# SoC_pwr_2.net
KiCad netlist of a schematic drawn in Altium Designer
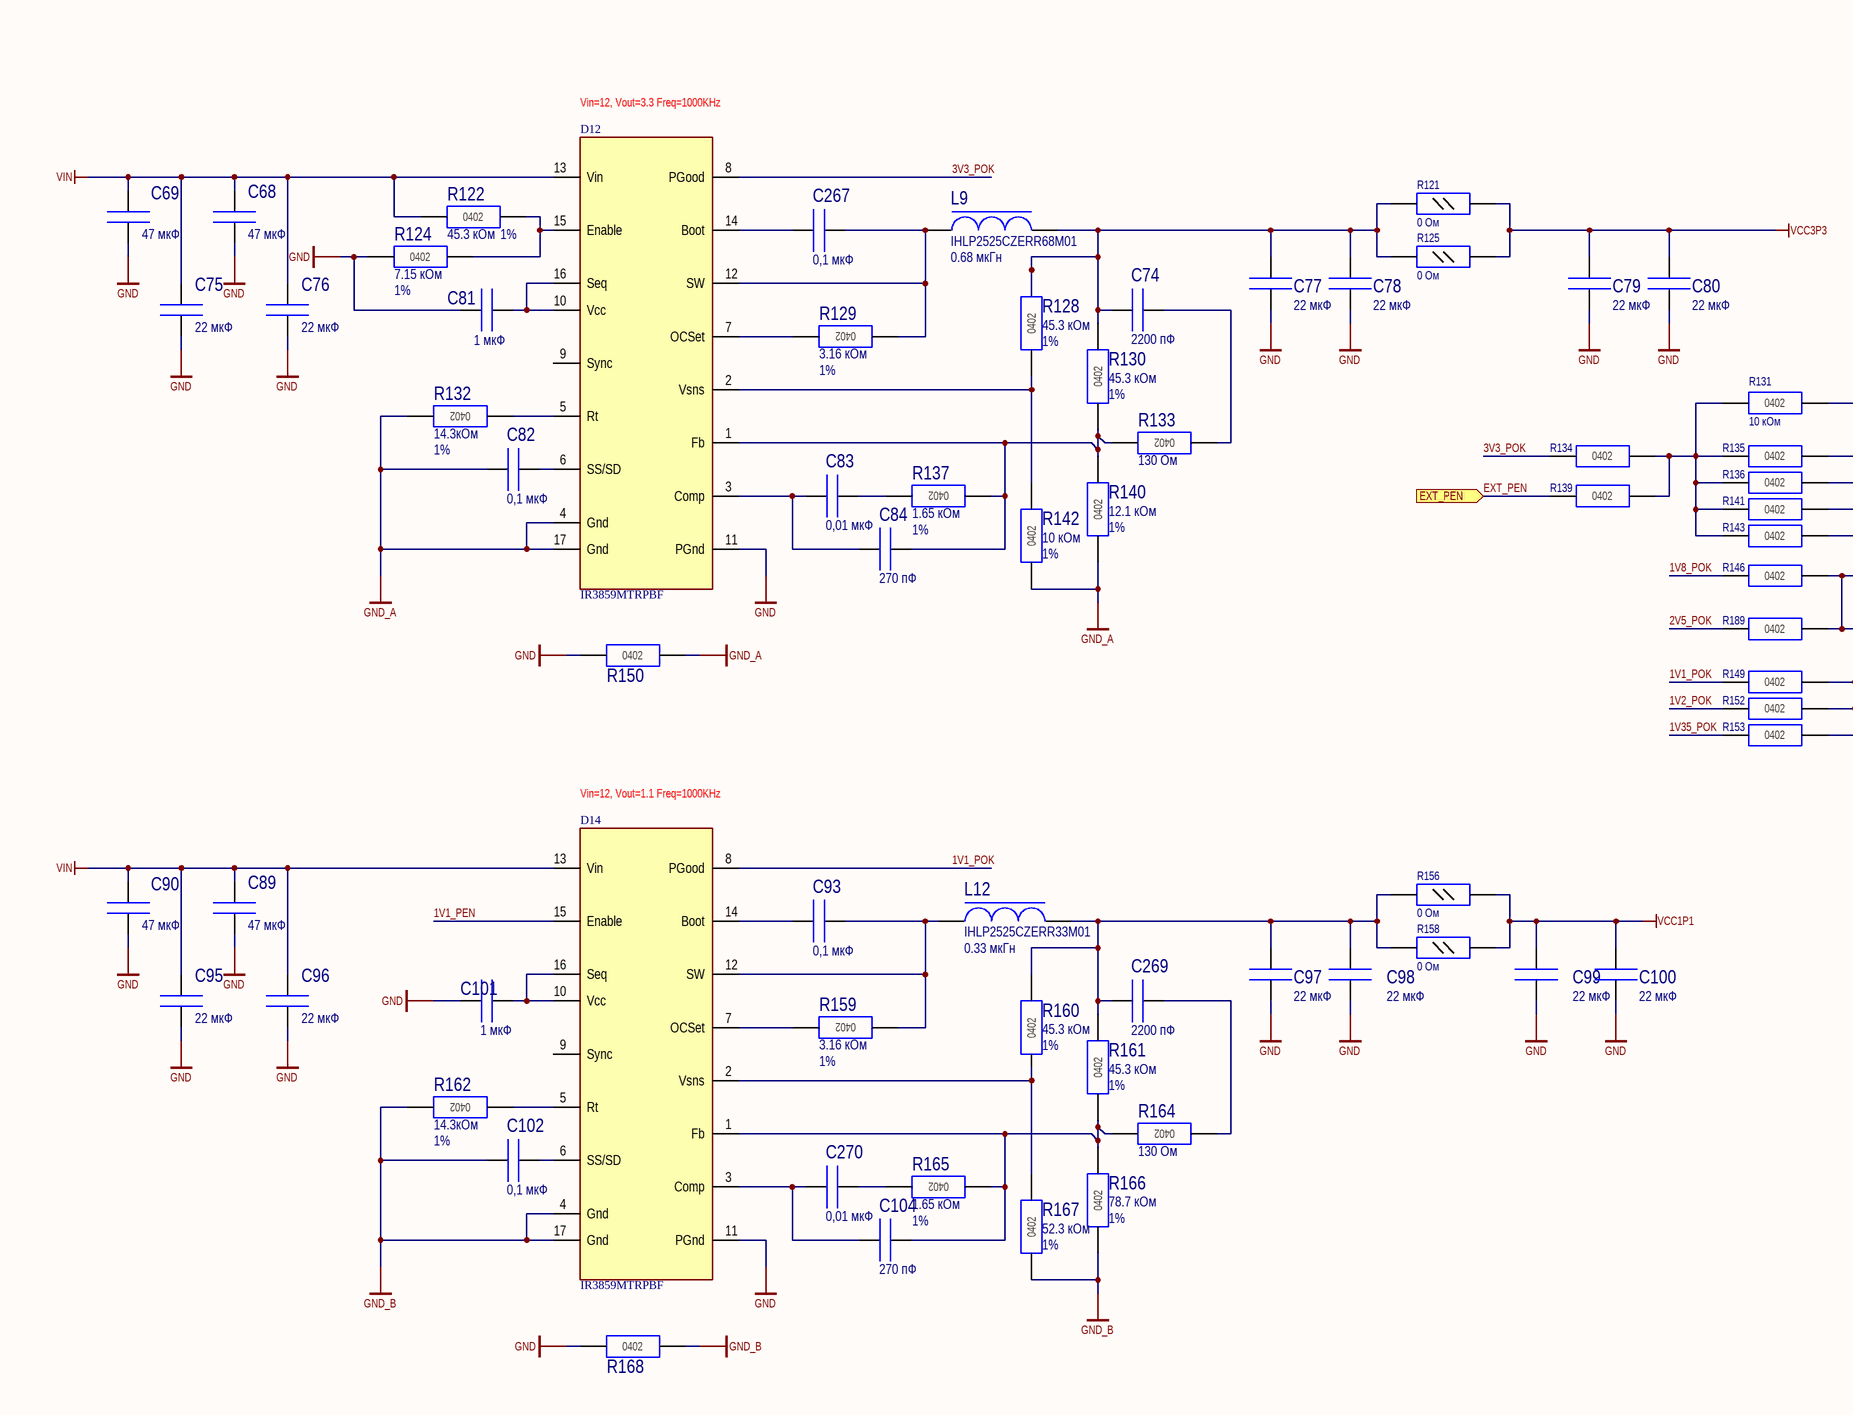
[diagram p0: SoC_pwr_2.SchDoc, left]
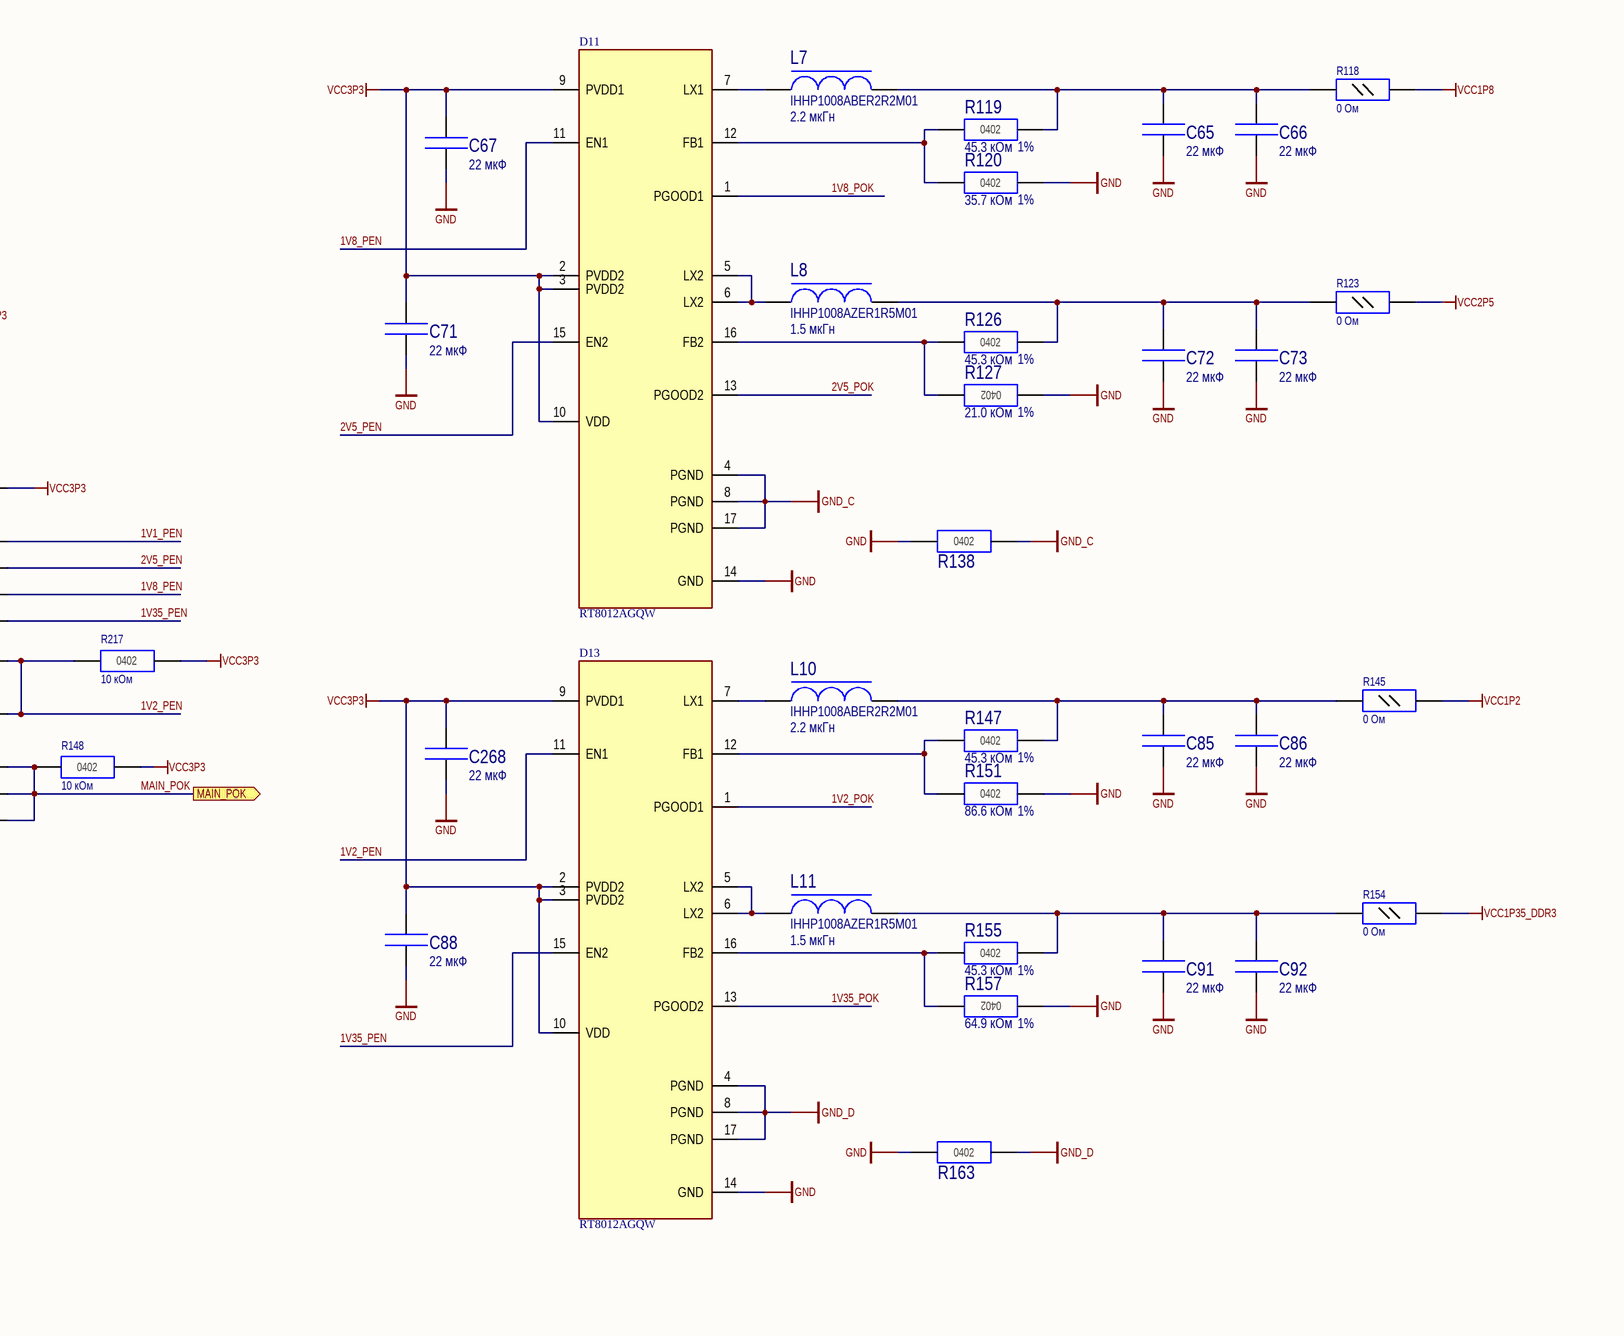
[diagram p1: SoC_pwr_2.SchDoc, right]

(export (version "E")
  (design (tool "Eeschema 10.0.6"))
  (components
    (comp (ref "C65")
      (value "22 мкФ")
      (footprint "CC0603")
      (description "Чип конденсатор керамический")
      (fields (field (name "Comment") "CC0603-X5R-22 мкФ-20%-6,3В"))
      (libsource (lib "Конденсаторы") (part "CC0603-X5R-#-20%-6,3В"))
    )
    (comp (ref "C66")
      (value "22 мкФ")
      (footprint "CC0603")
      (description "Чип конденсатор керамический")
      (fields (field (name "Comment") "CC0603-X5R-22 мкФ-20%-6,3В"))
      (libsource (lib "Конденсаторы") (part "CC0603-X5R-#-20%-6,3В"))
    )
    (comp (ref "C67")
      (value "22 мкФ")
      (footprint "CC0603")
      (description "Чип конденсатор керамический")
      (fields (field (name "Comment") "CC0603-X5R-22 мкФ-20%-6,3В"))
      (libsource (lib "Конденсаторы") (part "CC0603-X5R-#-20%-6,3В"))
    )
    (comp (ref "C68")
      (value "47 мкФ")
      (footprint "CC0603")
      (description "Чип конденсатор керамический")
      (fields (field (name "Comment") "CC0603-X5R-47 мкФ-20%-6,3В"))
      (libsource (lib "Конденсаторы") (part "CC0603-X5R-#-20%-6,3В"))
    )
    (comp (ref "C69")
      (value "47 мкФ")
      (footprint "CC0603")
      (description "Чип конденсатор керамический")
      (fields (field (name "Comment") "CC0603-X5R-47 мкФ-20%-6,3В"))
      (libsource (lib "Конденсаторы") (part "CC0603-X5R-#-20%-6,3В"))
    )
    (comp (ref "C71")
      (value "22 мкФ")
      (footprint "CC0603")
      (description "Чип конденсатор керамический")
      (fields (field (name "Comment") "CC0603-X5R-22 мкФ-20%-6,3В"))
      (libsource (lib "Конденсаторы") (part "CC0603-X5R-#-20%-6,3В"))
    )
    (comp (ref "C72")
      (value "22 мкФ")
      (footprint "CC0603")
      (description "Чип конденсатор керамический")
      (fields (field (name "Comment") "CC0603-X5R-22 мкФ-20%-6,3В"))
      (libsource (lib "Конденсаторы") (part "CC0603-X5R-#-20%-6,3В"))
    )
    (comp (ref "C73")
      (value "22 мкФ")
      (footprint "CC0603")
      (description "Чип конденсатор керамический")
      (fields (field (name "Comment") "CC0603-X5R-22 мкФ-20%-6,3В"))
      (libsource (lib "Конденсаторы") (part "CC0603-X5R-#-20%-6,3В"))
    )
    (comp (ref "C74")
      (value "2200 пФ")
      (footprint "CC0402(1005)")
      (description "Чип конденсатор керамический")
      (fields (field (name "Comment") "CC0402-X7R-2200 пФ-10%-16В"))
      (libsource (lib "Чип конденсаторы") (part "CC0402-X7R-#-20%-10В"))
    )
    (comp (ref "C75")
      (value "22 мкФ")
      (footprint "CC0603")
      (description "Чип конденсатор керамический")
      (fields (field (name "Comment") "CC0603-X5R-22 мкФ-20%-6,3В"))
      (libsource (lib "Конденсаторы") (part "CC0603-X5R-#-20%-6,3В"))
    )
    (comp (ref "C76")
      (value "22 мкФ")
      (footprint "CC0603")
      (description "Чип конденсатор керамический")
      (fields (field (name "Comment") "CC0603-X5R-22 мкФ-20%-6,3В"))
      (libsource (lib "Конденсаторы") (part "CC0603-X5R-#-20%-6,3В"))
    )
    (comp (ref "C77")
      (value "22 мкФ")
      (footprint "CC0603")
      (description "Чип конденсатор керамический")
      (fields (field (name "Comment") "CC0603-X5R-22 мкФ-20%-6,3В"))
      (libsource (lib "Конденсаторы") (part "CC0603-X5R-#-20%-6,3В"))
    )
    (comp (ref "C78")
      (value "22 мкФ")
      (footprint "CC0603")
      (description "Чип конденсатор керамический")
      (fields (field (name "Comment") "CC0603-X5R-22 мкФ-20%-6,3В"))
      (libsource (lib "Конденсаторы") (part "CC0603-X5R-#-20%-6,3В"))
    )
    (comp (ref "C79")
      (value "22 мкФ")
      (footprint "CC0603")
      (description "Чип конденсатор керамический")
      (fields (field (name "Comment") "CC0603-X5R-22 мкФ-20%-6,3В"))
      (libsource (lib "Конденсаторы") (part "CC0603-X5R-#-20%-6,3В"))
    )
    (comp (ref "C80")
      (value "22 мкФ")
      (footprint "CC0603")
      (description "Чип конденсатор керамический")
      (fields (field (name "Comment") "CC0603-X5R-22 мкФ-20%-6,3В"))
      (libsource (lib "Конденсаторы") (part "CC0603-X5R-#-20%-6,3В"))
    )
    (comp (ref "C81")
      (value "1 мкФ")
      (footprint "CC0603")
      (description "Чип конденсатор керамический")
      (fields (field (name "Comment") "CC0603-X5R-1 мкФ-10%-25В"))
      (libsource (lib "Конденсаторы") (part "CC0603-X5R-#-20%-6,3В"))
    )
    (comp (ref "C82")
      (value "0,1 мкФ")
      (footprint "CC0402(1005)")
      (description "Чип конденсатор керамический")
      (fields (field (name "Comment") "CC0402-X7R-0,1 мкФ-20%-10В"))
      (libsource (lib "Чип конденсаторы") (part "CC0402-X7R-#-20%-10В"))
    )
    (comp (ref "C83")
      (value "0,01 мкФ")
      (footprint "CC0402(1005)")
      (description "Чип конденсатор керамический")
      (fields (field (name "Comment") "CC0402-X7R-0,01 мкФ-10%-50В"))
      (libsource (lib "Чип конденсаторы") (part "CC0402-X7R-#-20%-10В"))
    )
    (comp (ref "C84")
      (value "270 пФ")
      (footprint "CC0402(1005)")
      (description "Чип конденсатор керамический")
      (fields (field (name "Comment") "CC0402-NP0-270 пФ-1%-50В"))
      (libsource (lib "Чип конденсаторы") (part "CC0402-X7R-#-20%-10В"))
    )
    (comp (ref "C85")
      (value "22 мкФ")
      (footprint "CC0603")
      (description "Чип конденсатор керамический")
      (fields (field (name "Comment") "CC0603-X5R-22 мкФ-20%-6,3В"))
      (libsource (lib "Конденсаторы") (part "CC0603-X5R-#-20%-6,3В"))
    )
    (comp (ref "C86")
      (value "22 мкФ")
      (footprint "CC0603")
      (description "Чип конденсатор керамический")
      (fields (field (name "Comment") "CC0603-X5R-22 мкФ-20%-6,3В"))
      (libsource (lib "Конденсаторы") (part "CC0603-X5R-#-20%-6,3В"))
    )
    (comp (ref "C88")
      (value "22 мкФ")
      (footprint "CC0603")
      (description "Чип конденсатор керамический")
      (fields (field (name "Comment") "CC0603-X5R-22 мкФ-20%-6,3В"))
      (libsource (lib "Конденсаторы") (part "CC0603-X5R-#-20%-6,3В"))
    )
    (comp (ref "C89")
      (value "47 мкФ")
      (footprint "CC0603")
      (description "Чип конденсатор керамический")
      (fields (field (name "Comment") "CC0603-X5R-47 мкФ-20%-6,3В"))
      (libsource (lib "Конденсаторы") (part "CC0603-X5R-#-20%-6,3В"))
    )
    (comp (ref "C90")
      (value "47 мкФ")
      (footprint "CC0603")
      (description "Чип конденсатор керамический")
      (fields (field (name "Comment") "CC0603-X5R-47 мкФ-20%-6,3В"))
      (libsource (lib "Конденсаторы") (part "CC0603-X5R-#-20%-6,3В"))
    )
    (comp (ref "C91")
      (value "22 мкФ")
      (footprint "CC0603")
      (description "Чип конденсатор керамический")
      (fields (field (name "Comment") "CC0603-X5R-22 мкФ-20%-6,3В"))
      (libsource (lib "Конденсаторы") (part "CC0603-X5R-#-20%-6,3В"))
    )
    (comp (ref "C92")
      (value "22 мкФ")
      (footprint "CC0603")
      (description "Чип конденсатор керамический")
      (fields (field (name "Comment") "CC0603-X5R-22 мкФ-20%-6,3В"))
      (libsource (lib "Конденсаторы") (part "CC0603-X5R-#-20%-6,3В"))
    )
    (comp (ref "C93")
      (value "0,1 мкФ")
      (footprint "CC0402(1005)")
      (description "Чип конденсатор керамический")
      (fields (field (name "Comment") "CC0402-X7R-0,1 мкФ-20%-10В"))
      (libsource (lib "Чип конденсаторы") (part "CC0402-X7R-#-20%-10В"))
    )
    (comp (ref "C95")
      (value "22 мкФ")
      (footprint "CC0603")
      (description "Чип конденсатор керамический")
      (fields (field (name "Comment") "CC0603-X5R-22 мкФ-20%-6,3В"))
      (libsource (lib "Конденсаторы") (part "CC0603-X5R-#-20%-6,3В"))
    )
    (comp (ref "C96")
      (value "22 мкФ")
      (footprint "CC0603")
      (description "Чип конденсатор керамический")
      (fields (field (name "Comment") "CC0603-X5R-22 мкФ-20%-6,3В"))
      (libsource (lib "Конденсаторы") (part "CC0603-X5R-#-20%-6,3В"))
    )
    (comp (ref "C97")
      (value "22 мкФ")
      (footprint "CC0603")
      (description "Чип конденсатор керамический")
      (fields (field (name "Comment") "CC0603-X5R-22 мкФ-20%-6,3В"))
      (libsource (lib "Конденсаторы") (part "CC0603-X5R-#-20%-6,3В"))
    )
    (comp (ref "C98")
      (value "22 мкФ")
      (footprint "CC0603")
      (description "Чип конденсатор керамический")
      (fields (field (name "Comment") "CC0603-X5R-22 мкФ-20%-6,3В"))
      (libsource (lib "Конденсаторы") (part "CC0603-X5R-#-20%-6,3В"))
    )
    (comp (ref "C99")
      (value "22 мкФ")
      (footprint "CC0603")
      (description "Чип конденсатор керамический")
      (fields (field (name "Comment") "CC0603-X5R-22 мкФ-20%-6,3В"))
      (libsource (lib "Конденсаторы") (part "CC0603-X5R-#-20%-6,3В"))
    )
    (comp (ref "C100")
      (value "22 мкФ")
      (footprint "CC0603")
      (description "Чип конденсатор керамический")
      (fields (field (name "Comment") "CC0603-X5R-22 мкФ-20%-6,3В"))
      (libsource (lib "Конденсаторы") (part "CC0603-X5R-#-20%-6,3В"))
    )
    (comp (ref "C101")
      (value "1 мкФ")
      (footprint "CC0603")
      (description "Чип конденсатор керамический")
      (fields (field (name "Comment") "CC0603-X5R-1 мкФ-10%-25В"))
      (libsource (lib "Конденсаторы") (part "CC0603-X5R-#-20%-6,3В"))
    )
    (comp (ref "C102")
      (value "0,1 мкФ")
      (footprint "CC0402(1005)")
      (description "Чип конденсатор керамический")
      (fields (field (name "Comment") "CC0402-X7R-0,1 мкФ-20%-10В"))
      (libsource (lib "Чип конденсаторы") (part "CC0402-X7R-#-20%-10В"))
    )
    (comp (ref "C104")
      (value "270 пФ")
      (footprint "CC0402(1005)")
      (description "Чип конденсатор керамический")
      (fields (field (name "Comment") "CC0402-NP0-270 пФ-1%-50В"))
      (libsource (lib "Чип конденсаторы") (part "CC0402-X7R-#-20%-10В"))
    )
    (comp (ref "C267")
      (value "0,1 мкФ")
      (footprint "CC0402(1005)")
      (description "Чип конденсатор керамический")
      (fields (field (name "Comment") "CC0402-X7R-0,1 мкФ-20%-10В"))
      (libsource (lib "Чип конденсаторы") (part "CC0402-X7R-#-20%-10В"))
    )
    (comp (ref "C268")
      (value "22 мкФ")
      (footprint "CC0603")
      (description "Чип конденсатор керамический")
      (fields (field (name "Comment") "CC0603-X5R-22 мкФ-20%-6,3В"))
      (libsource (lib "Конденсаторы") (part "CC0603-X5R-#-20%-6,3В"))
    )
    (comp (ref "C269")
      (value "2200 пФ")
      (footprint "CC0402(1005)")
      (description "Чип конденсатор керамический")
      (fields (field (name "Comment") "CC0402-X7R-2200 пФ-10%-16В"))
      (libsource (lib "Чип конденсаторы") (part "CC0402-X7R-#-20%-10В"))
    )
    (comp (ref "C270")
      (value "0,01 мкФ")
      (footprint "CC0402(1005)")
      (description "Чип конденсатор керамический")
      (fields (field (name "Comment") "CC0402-X7R-0,01 мкФ-10%-50В"))
      (libsource (lib "Чип конденсаторы") (part "CC0402-X7R-#-20%-10В"))
    )
    (comp (ref "D11")
      (value "RT8012AGQW")
      (footprint "RT8012AGQW")
      (libsource (lib "SD_IC") (part "RT8012AGQW"))
    )
    (comp (ref "D12")
      (value "IR3859MTRPBF")
      (footprint "IR3859")
      (description "IC REG BUCK ADJ 9A SYNC 17PQFN")
      (libsource (lib "SD_IC") (part "IR3859MPbF"))
    )
    (comp (ref "D13")
      (value "RT8012AGQW")
      (footprint "RT8012AGQW")
      (libsource (lib "SD_IC") (part "RT8012AGQW"))
    )
    (comp (ref "D14")
      (value "IR3859MTRPBF")
      (footprint "IR3859")
      (description "IC REG BUCK ADJ 9A SYNC 17PQFN")
      (libsource (lib "SD_IC") (part "IR3859MPbF"))
    )
    (comp (ref "L7")
      (value "IHHP1008ABER2R2M01")
      (footprint "INDC2720X12L")
      (description "FIXED IND 2.2UH 2.3A 90 MOHM SMD")
      (fields (field (name "ALTIUM_VALUE") "2.2 мкГн"))
      (libsource (lib "SD_IC") (part "L_VISH_IIHHP1008ABE"))
    )
    (comp (ref "L8")
      (value "IHHP1008AZER1R5M01")
      (footprint "INDC2720X12L")
      (description "FIXED IND 1.5UH 2.4A 96 MOHM SMD")
      (fields (field (name "ALTIUM_VALUE") "1.5 мкГн"))
      (libsource (lib "SD_IC") (part "L_VISH_IIHHP1008ABE_1"))
    )
    (comp (ref "L9")
      (value "IHLP2525CZERR68M01")
      (footprint "INDP6965X30L")
      (description "FIXED IND 680NH 15.5A 5.5 MOHM")
      (fields (field (name "ALTIUM_VALUE") "0.68 мкГн"))
      (libsource (lib "SD_IC") (part "L_VISH_IHLP2525CZERR68M01"))
    )
    (comp (ref "L10")
      (value "IHHP1008ABER2R2M01")
      (footprint "INDC2720X12L")
      (description "FIXED IND 2.2UH 2.3A 90 MOHM SMD")
      (fields (field (name "ALTIUM_VALUE") "2.2 мкГн"))
      (libsource (lib "SD_IC") (part "L_VISH_IIHHP1008ABE"))
    )
    (comp (ref "L11")
      (value "IHHP1008AZER1R5M01")
      (footprint "INDC2720X12L")
      (description "FIXED IND 1.5UH 2.4A 96 MOHM SMD")
      (fields (field (name "ALTIUM_VALUE") "1.5 мкГн"))
      (libsource (lib "SD_IC") (part "L_VISH_IIHHP1008ABE_1"))
    )
    (comp (ref "L12")
      (value "IHLP2525CZERR33M01")
      (footprint "INDP6965X30L")
      (description "FIXED IND 680NH 15.5A 5.5 MOHM")
      (fields (field (name "ALTIUM_VALUE") "0.33 мкГн"))
      (libsource (lib "SD_IC") (part "L_VISH_IHLP2525CZERR68M01"))
    )
    (comp (ref "R118")
      (value "0 Ом")
      (footprint "CR0805")
      (description "Чип резистор")
      (fields (field (name "Comment") "CR0805-0 Ом-±5%"))
      (libsource (lib "Резисторы") (part "CR0805-#-±5%"))
    )
    (comp (ref "R119")
      (value "45.3 кОм")
      (footprint "CR0402(1005)")
      (description "Чип резистор")
      (fields (field (name "TOLERANCE") "1%") (field (name "Comment") "CR0402-45.3 кОм-±1%"))
      (libsource (lib "Чип резисторы") (part "CR0402-#-±1%"))
    )
    (comp (ref "R120")
      (value "35.7 кОм")
      (footprint "CR0402(1005)")
      (description "Чип резистор")
      (fields (field (name "TOLERANCE") "1%") (field (name "Comment") "CR0402-35.7 кОм-±1%"))
      (libsource (lib "Чип резисторы") (part "CR0402-#-±1%"))
    )
    (comp (ref "R121")
      (value "0 Ом")
      (footprint "CR0805")
      (description "Чип резистор")
      (fields (field (name "Comment") "CR0805-0 Ом-±5%"))
      (libsource (lib "Резисторы") (part "CR0805-#-±5%"))
    )
    (comp (ref "R122")
      (value "45.3 кОм")
      (footprint "CR0402(1005)")
      (description "Чип резистор")
      (fields (field (name "TOLERANCE") "1%") (field (name "Comment") "CR0402-45.3 кОм-±1%"))
      (libsource (lib "Чип резисторы") (part "CR0402-#-±1%"))
    )
    (comp (ref "R123")
      (value "0 Ом")
      (footprint "CR0805")
      (description "Чип резистор")
      (fields (field (name "Comment") "CR0805-0 Ом-±5%"))
      (libsource (lib "Резисторы") (part "CR0805-#-±5%"))
    )
    (comp (ref "R124")
      (value "7.15 кОм")
      (footprint "CR0402(1005)")
      (description "Чип резистор")
      (fields (field (name "TOLERANCE") "1%") (field (name "Comment") "CR0402-7.15 кОм-±1%"))
      (libsource (lib "Чип резисторы") (part "CR0402-#-±1%"))
    )
    (comp (ref "R125")
      (value "0 Ом")
      (footprint "CR0805")
      (description "Чип резистор")
      (fields (field (name "Comment") "CR0805-0 Ом-±5%"))
      (libsource (lib "Резисторы") (part "CR0805-#-±5%"))
    )
    (comp (ref "R126")
      (value "45.3 кОм")
      (footprint "CR0402(1005)")
      (description "Чип резистор")
      (fields (field (name "TOLERANCE") "1%") (field (name "Comment") "CR0402-45.3 кОм-±1%"))
      (libsource (lib "Чип резисторы") (part "CR0402-#-±1%"))
    )
    (comp (ref "R127")
      (value "21.0 кОм")
      (footprint "CR0402(1005)")
      (description "Чип резистор")
      (fields (field (name "TOLERANCE") "1%") (field (name "Comment") "CR0402-21.0 кОм-±1%"))
      (libsource (lib "") (part "CR0402-#-±1%_1"))
    )
    (comp (ref "R128")
      (value "45.3 кОм")
      (footprint "CR0402(1005)")
      (description "Чип резистор")
      (fields (field (name "TOLERANCE") "1%") (field (name "Comment") "CR0402-45.3 кОм-±1%"))
      (libsource (lib "") (part "CR0402-#-±1%_2"))
    )
    (comp (ref "R129")
      (value "3.16 кОм")
      (footprint "CR0402(1005)")
      (description "Чип резистор")
      (fields (field (name "TOLERANCE") "1%") (field (name "Comment") "CR0402-3.16 кОм-±1%"))
      (libsource (lib "") (part "CR0402-#-±1%_1"))
    )
    (comp (ref "R130")
      (value "45.3 кОм")
      (footprint "CR0402(1005)")
      (description "Чип резистор")
      (fields (field (name "TOLERANCE") "1%") (field (name "Comment") "CR0402-45.3 кОм-±1%"))
      (libsource (lib "") (part "CR0402-#-±1%_2"))
    )
    (comp (ref "R131")
      (value "10 кОм")
      (footprint "CR0402(1005)")
      (description "Чип резистор")
      (fields (field (name "TOLERANCE") "5%") (field (name "Comment") "CR0402-10 кОм-±5%"))
      (libsource (lib "Резисторы") (part "CR0402-#-±5%"))
    )
    (comp (ref "R132")
      (value "14.3кОм")
      (footprint "CR0402(1005)")
      (description "Чип резистор")
      (fields (field (name "TOLERANCE") "1%") (field (name "Comment") "CR0402-14.3кОм-±1%"))
      (libsource (lib "") (part "CR0402-#-±1%_1"))
    )
    (comp (ref "R133")
      (value "130 Ом")
      (footprint "CR0402(1005)")
      (description "Чип резистор")
      (fields (field (name "Comment") "CR0402-130 Ом-±1%"))
      (libsource (lib "") (part "CR0402-#-±1%_1"))
    )
    (comp (ref "R134")
      (value "CR0402-0 Ом-±5%")
      (footprint "CR0402(1005)")
      (description "Чип резистор")
      (fields (field (name "TOLERANCE") "5%"))
      (libsource (lib "Резисторы") (part "CR0402-#-±5%"))
    )
    (comp (ref "R135")
      (value "CR0402-0 Ом-±5%")
      (footprint "CR0402(1005)")
      (description "Чип резистор")
      (fields (field (name "TOLERANCE") "5%"))
      (libsource (lib "Резисторы") (part "CR0402-#-±5%"))
    )
    (comp (ref "R136")
      (value "CR0402-0 Ом-±5%")
      (footprint "CR0402(1005)")
      (description "Чип резистор")
      (fields (field (name "TOLERANCE") "5%"))
      (libsource (lib "Резисторы") (part "CR0402-#-±5%"))
    )
    (comp (ref "R137")
      (value "1.65 кОм")
      (footprint "CR0402(1005)")
      (description "Чип резистор")
      (fields (field (name "TOLERANCE") "1%") (field (name "Comment") "CR0402-1.65 кОм-±1%"))
      (libsource (lib "") (part "CR0402-#-±1%_1"))
    )
    (comp (ref "R138")
      (value "CR0402-0 Ом-±5%")
      (footprint "CR0402(1005)")
      (description "Чип резистор")
      (fields (field (name "TOLERANCE") "5%"))
      (libsource (lib "Резисторы") (part "CR0402-#-±5%"))
    )
    (comp (ref "R139")
      (value "CR0402-0 Ом-±5%")
      (footprint "CR0402(1005)")
      (description "Чип резистор")
      (fields (field (name "TOLERANCE") "5%"))
      (libsource (lib "Резисторы") (part "CR0402-#-±5%"))
    )
    (comp (ref "R140")
      (value "12.1 кОм")
      (footprint "CR0402(1005)")
      (description "Чип резистор")
      (fields (field (name "TOLERANCE") "1%") (field (name "Comment") "CR0402-12.1 кОм-±1%"))
      (libsource (lib "") (part "CR0402-#-±1%_2"))
    )
    (comp (ref "R141")
      (value "CR0402-0 Ом-±5%")
      (footprint "CR0402(1005)")
      (description "Чип резистор")
      (fields (field (name "TOLERANCE") "5%"))
      (libsource (lib "Резисторы") (part "CR0402-#-±5%"))
    )
    (comp (ref "R142")
      (value "10 кОм")
      (footprint "CR0402(1005)")
      (description "Чип резистор")
      (fields (field (name "TOLERANCE") "1%") (field (name "Comment") "CR0402-10 кОм-±1%"))
      (libsource (lib "") (part "CR0402-#-±1%_2"))
    )
    (comp (ref "R143")
      (value "CR0402-0 Ом-±5%")
      (footprint "CR0402(1005)")
      (description "Чип резистор")
      (fields (field (name "TOLERANCE") "5%"))
      (libsource (lib "Резисторы") (part "CR0402-#-±5%"))
    )
    (comp (ref "R145")
      (value "0 Ом")
      (footprint "CR0805")
      (description "Чип резистор")
      (fields (field (name "Comment") "CR0805-0 Ом-±5%"))
      (libsource (lib "Резисторы") (part "CR0805-#-±5%"))
    )
    (comp (ref "R146")
      (value "CR0402-0 Ом-±5%")
      (footprint "CR0402(1005)")
      (description "Чип резистор")
      (fields (field (name "TOLERANCE") "5%"))
      (libsource (lib "Резисторы") (part "CR0402-#-±5%"))
    )
    (comp (ref "R147")
      (value "45.3 кОм")
      (footprint "CR0402(1005)")
      (description "Чип резистор")
      (fields (field (name "TOLERANCE") "1%") (field (name "Comment") "CR0402-45.3 кОм-±1%"))
      (libsource (lib "Чип резисторы") (part "CR0402-#-±1%"))
    )
    (comp (ref "R148")
      (value "10 кОм")
      (footprint "CR0402(1005)")
      (description "Чип резистор")
      (fields (field (name "TOLERANCE") "5%") (field (name "Comment") "CR0402-10 кОм-±5%"))
      (libsource (lib "Резисторы") (part "CR0402-#-±5%"))
    )
    (comp (ref "R149")
      (value "CR0402-0 Ом-±5%")
      (footprint "CR0402(1005)")
      (description "Чип резистор")
      (fields (field (name "TOLERANCE") "5%"))
      (libsource (lib "Резисторы") (part "CR0402-#-±5%"))
    )
    (comp (ref "R150")
      (value "CR0402-0 Ом-±5%")
      (footprint "CR0402(1005)")
      (description "Чип резистор")
      (fields (field (name "TOLERANCE") "5%"))
      (libsource (lib "Резисторы") (part "CR0402-#-±5%"))
    )
    (comp (ref "R151")
      (value "86.6 кОм")
      (footprint "CR0402(1005)")
      (description "Чип резистор")
      (fields (field (name "TOLERANCE") "1%") (field (name "Comment") "CR0402-86.6 кОм-±1%"))
      (libsource (lib "Чип резисторы") (part "CR0402-#-±1%"))
    )
    (comp (ref "R152")
      (value "CR0402-0 Ом-±5%")
      (footprint "CR0402(1005)")
      (description "Чип резистор")
      (fields (field (name "TOLERANCE") "5%"))
      (libsource (lib "Резисторы") (part "CR0402-#-±5%"))
    )
    (comp (ref "R153")
      (value "CR0402-0 Ом-±5%")
      (footprint "CR0402(1005)")
      (description "Чип резистор")
      (fields (field (name "TOLERANCE") "5%"))
      (libsource (lib "Резисторы") (part "CR0402-#-±5%"))
    )
    (comp (ref "R154")
      (value "0 Ом")
      (footprint "CR0805")
      (description "Чип резистор")
      (fields (field (name "Comment") "CR0805-0 Ом-±5%"))
      (libsource (lib "Резисторы") (part "CR0805-#-±5%"))
    )
    (comp (ref "R155")
      (value "45.3 кОм")
      (footprint "CR0402(1005)")
      (description "Чип резистор")
      (fields (field (name "TOLERANCE") "1%") (field (name "Comment") "CR0402-45.3 кОм-±1%"))
      (libsource (lib "Чип резисторы") (part "CR0402-#-±1%"))
    )
    (comp (ref "R156")
      (value "0 Ом")
      (footprint "CR0805")
      (description "Чип резистор")
      (fields (field (name "Comment") "CR0805-0 Ом-±5%"))
      (libsource (lib "Резисторы") (part "CR0805-#-±5%"))
    )
    (comp (ref "R157")
      (value "64.9 кОм")
      (footprint "CR0402(1005)")
      (description "Чип резистор")
      (fields (field (name "TOLERANCE") "1%") (field (name "Comment") "CR0402-64.9 кОм-±1%"))
      (libsource (lib "") (part "CR0402-#-±1%_1"))
    )
    (comp (ref "R158")
      (value "0 Ом")
      (footprint "CR0805")
      (description "Чип резистор")
      (fields (field (name "Comment") "CR0805-0 Ом-±5%"))
      (libsource (lib "Резисторы") (part "CR0805-#-±5%"))
    )
    (comp (ref "R159")
      (value "3.16 кОм")
      (footprint "CR0402(1005)")
      (description "Чип резистор")
      (fields (field (name "TOLERANCE") "1%") (field (name "Comment") "CR0402-3.16 кОм-±1%"))
      (libsource (lib "") (part "CR0402-#-±1%_1"))
    )
    (comp (ref "R160")
      (value "45.3 кОм")
      (footprint "CR0402(1005)")
      (description "Чип резистор")
      (fields (field (name "TOLERANCE") "1%") (field (name "Comment") "CR0402-45.3 кОм-±1%"))
      (libsource (lib "") (part "CR0402-#-±1%_2"))
    )
    (comp (ref "R161")
      (value "45.3 кОм")
      (footprint "CR0402(1005)")
      (description "Чип резистор")
      (fields (field (name "TOLERANCE") "1%") (field (name "Comment") "CR0402-45.3 кОм-±1%"))
      (libsource (lib "") (part "CR0402-#-±1%_2"))
    )
    (comp (ref "R162")
      (value "14.3кОм")
      (footprint "CR0402(1005)")
      (description "Чип резистор")
      (fields (field (name "TOLERANCE") "1%") (field (name "Comment") "CR0402-14.3кОм-±1%"))
      (libsource (lib "") (part "CR0402-#-±1%_1"))
    )
    (comp (ref "R163")
      (value "CR0402-0 Ом-±5%")
      (footprint "CR0402(1005)")
      (description "Чип резистор")
      (fields (field (name "TOLERANCE") "5%"))
      (libsource (lib "Резисторы") (part "CR0402-#-±5%"))
    )
    (comp (ref "R164")
      (value "130 Ом")
      (footprint "CR0402(1005)")
      (description "Чип резистор")
      (fields (field (name "Comment") "CR0402-130 Ом-±1%"))
      (libsource (lib "") (part "CR0402-#-±1%_1"))
    )
    (comp (ref "R165")
      (value "1.65 кОм")
      (footprint "CR0402(1005)")
      (description "Чип резистор")
      (fields (field (name "TOLERANCE") "1%") (field (name "Comment") "CR0402-1.65 кОм-±1%"))
      (libsource (lib "") (part "CR0402-#-±1%_1"))
    )
    (comp (ref "R166")
      (value "78.7 кОм")
      (footprint "CR0402(1005)")
      (description "Чип резистор")
      (fields (field (name "TOLERANCE") "1%") (field (name "Comment") "CR0402-78.7 кОм-±1%"))
      (libsource (lib "") (part "CR0402-#-±1%_2"))
    )
    (comp (ref "R167")
      (value "52.3 кОм")
      (footprint "CR0402(1005)")
      (description "Чип резистор")
      (fields (field (name "TOLERANCE") "1%") (field (name "Comment") "CR0402-52.3 кОм-±1%"))
      (libsource (lib "") (part "CR0402-#-±1%_2"))
    )
    (comp (ref "R168")
      (value "CR0402-0 Ом-±5%")
      (footprint "CR0402(1005)")
      (description "Чип резистор")
      (fields (field (name "TOLERANCE") "5%"))
      (libsource (lib "Резисторы") (part "CR0402-#-±5%"))
    )
    (comp (ref "R189")
      (value "CR0402-0 Ом-±5%")
      (footprint "CR0402(1005)")
      (description "Чип резистор")
      (fields (field (name "TOLERANCE") "5%"))
      (libsource (lib "Резисторы") (part "CR0402-#-±5%"))
    )
    (comp (ref "R217")
      (value "10 кОм")
      (footprint "CR0402(1005)")
      (description "Чип резистор")
      (fields (field (name "TOLERANCE") "5%") (field (name "Comment") "CR0402-10 кОм-±5%"))
      (libsource (lib "Резисторы") (part "CR0402-#-±5%"))
    )
  )
  (nets
    (net (code "1") (name "/1V1_PEN") (class "Default")
      (node (ref "D14") (pin "15") (pinfunction "Enable_15") (pintype "passive"))
      (node (ref "R135") (pin "2") (pinfunction "-_2") (pintype "passive"))
    )
    (net (code "2") (name "/1V1_POK") (class "Default")
      (node (ref "D14") (pin "8") (pinfunction "PGood_8") (pintype "passive"))
      (node (ref "R149") (pin "1") (pinfunction "+_1") (pintype "passive"))
    )
    (net (code "3") (name "/1V2_PEN") (class "Default")
      (node (ref "D13") (pin "11") (pinfunction "EN1_11") (pintype "passive"))
      (node (ref "R146") (pin "2") (pinfunction "-_2") (pintype "passive"))
      (node (ref "R189") (pin "2") (pinfunction "-_2") (pintype "passive"))
      (node (ref "R217") (pin "1") (pinfunction "+_1") (pintype "passive"))
    )
    (net (code "4") (name "/1V2_POK") (class "Default")
      (node (ref "D13") (pin "1") (pinfunction "PGOOD1_1") (pintype "passive"))
      (node (ref "R152") (pin "1") (pinfunction "+_1") (pintype "passive"))
    )
    (net (code "5") (name "/1V8_PEN") (class "Default")
      (node (ref "D11") (pin "11") (pinfunction "EN1_11") (pintype "passive"))
      (node (ref "R141") (pin "2") (pinfunction "-_2") (pintype "passive"))
    )
    (net (code "6") (name "/1V8_POK") (class "Default")
      (node (ref "D11") (pin "1") (pinfunction "PGOOD1_1") (pintype "passive"))
      (node (ref "R146") (pin "1") (pinfunction "+_1") (pintype "passive"))
    )
    (net (code "7") (name "/1V35_PEN") (class "Default")
      (node (ref "D13") (pin "15") (pinfunction "EN2_15") (pintype "passive"))
      (node (ref "R143") (pin "2") (pinfunction "-_2") (pintype "passive"))
    )
    (net (code "8") (name "/1V35_POK") (class "Default")
      (node (ref "D13") (pin "13") (pinfunction "PGOOD2_13") (pintype "passive"))
      (node (ref "R153") (pin "1") (pinfunction "+_1") (pintype "passive"))
    )
    (net (code "9") (name "/2V5_PEN") (class "Default")
      (node (ref "D11") (pin "15") (pinfunction "EN2_15") (pintype "passive"))
      (node (ref "R136") (pin "2") (pinfunction "-_2") (pintype "passive"))
    )
    (net (code "10") (name "/2V5_POK") (class "Default")
      (node (ref "D11") (pin "13") (pinfunction "PGOOD2_13") (pintype "passive"))
      (node (ref "R189") (pin "1") (pinfunction "+_1") (pintype "passive"))
    )
    (net (code "11") (name "/3V3_POK") (class "Default")
      (node (ref "D12") (pin "8") (pinfunction "PGood_8") (pintype "passive"))
      (node (ref "R134") (pin "1") (pinfunction "+_1") (pintype "passive"))
    )
    (net (code "12") (name "/EXT_PEN") (class "Default")
      (node (ref "R139") (pin "1") (pinfunction "+_1") (pintype "passive"))
    )
    (net (code "13") (name "/MAIN_POK") (class "Default")
      (node (ref "R148") (pin "1") (pinfunction "+_1") (pintype "passive"))
      (node (ref "R149") (pin "2") (pinfunction "-_2") (pintype "passive"))
      (node (ref "R152") (pin "2") (pinfunction "-_2") (pintype "passive"))
      (node (ref "R153") (pin "2") (pinfunction "-_2") (pintype "passive"))
    )
    (net (code "14") (name "GND") (class "Default")
      (node (ref "C100") (pin "2") (pinfunction "-_2") (pintype "passive"))
      (node (ref "C101") (pin "1") (pinfunction "+_1") (pintype "passive"))
      (node (ref "C268") (pin "2") (pinfunction "-_2") (pintype "passive"))
      (node (ref "C65") (pin "2") (pinfunction "-_2") (pintype "passive"))
      (node (ref "C66") (pin "2") (pinfunction "-_2") (pintype "passive"))
      (node (ref "C67") (pin "2") (pinfunction "-_2") (pintype "passive"))
      (node (ref "C68") (pin "2") (pinfunction "-_2") (pintype "passive"))
      (node (ref "C69") (pin "2") (pinfunction "-_2") (pintype "passive"))
      (node (ref "C71") (pin "2") (pinfunction "-_2") (pintype "passive"))
      (node (ref "C72") (pin "2") (pinfunction "-_2") (pintype "passive"))
      (node (ref "C73") (pin "2") (pinfunction "-_2") (pintype "passive"))
      (node (ref "C75") (pin "2") (pinfunction "-_2") (pintype "passive"))
      (node (ref "C76") (pin "2") (pinfunction "-_2") (pintype "passive"))
      (node (ref "C77") (pin "2") (pinfunction "-_2") (pintype "passive"))
      (node (ref "C78") (pin "2") (pinfunction "-_2") (pintype "passive"))
      (node (ref "C79") (pin "2") (pinfunction "-_2") (pintype "passive"))
      (node (ref "C80") (pin "2") (pinfunction "-_2") (pintype "passive"))
      (node (ref "C81") (pin "1") (pinfunction "+_1") (pintype "passive"))
      (node (ref "C85") (pin "2") (pinfunction "-_2") (pintype "passive"))
      (node (ref "C86") (pin "2") (pinfunction "-_2") (pintype "passive"))
      (node (ref "C88") (pin "2") (pinfunction "-_2") (pintype "passive"))
      (node (ref "C89") (pin "2") (pinfunction "-_2") (pintype "passive"))
      (node (ref "C90") (pin "2") (pinfunction "-_2") (pintype "passive"))
      (node (ref "C91") (pin "2") (pinfunction "-_2") (pintype "passive"))
      (node (ref "C92") (pin "2") (pinfunction "-_2") (pintype "passive"))
      (node (ref "C95") (pin "2") (pinfunction "-_2") (pintype "passive"))
      (node (ref "C96") (pin "2") (pinfunction "-_2") (pintype "passive"))
      (node (ref "C97") (pin "2") (pinfunction "-_2") (pintype "passive"))
      (node (ref "C98") (pin "2") (pinfunction "-_2") (pintype "passive"))
      (node (ref "C99") (pin "2") (pinfunction "-_2") (pintype "passive"))
      (node (ref "D11") (pin "14") (pinfunction "GND_14") (pintype "passive"))
      (node (ref "D12") (pin "11") (pinfunction "PGnd_11") (pintype "passive"))
      (node (ref "D13") (pin "14") (pinfunction "GND_14") (pintype "passive"))
      (node (ref "D14") (pin "11") (pinfunction "PGnd_11") (pintype "passive"))
      (node (ref "R120") (pin "2") (pinfunction "-_2") (pintype "passive"))
      (node (ref "R124") (pin "1") (pinfunction "+_1") (pintype "passive"))
      (node (ref "R127") (pin "1") (pinfunction "+_1") (pintype "passive"))
      (node (ref "R138") (pin "1") (pinfunction "+_1") (pintype "passive"))
      (node (ref "R150") (pin "1") (pinfunction "+_1") (pintype "passive"))
      (node (ref "R151") (pin "2") (pinfunction "-_2") (pintype "passive"))
      (node (ref "R157") (pin "1") (pinfunction "+_1") (pintype "passive"))
      (node (ref "R163") (pin "1") (pinfunction "+_1") (pintype "passive"))
      (node (ref "R168") (pin "1") (pinfunction "+_1") (pintype "passive"))
    )
    (net (code "15") (name "GND_A") (class "Default")
      (node (ref "C82") (pin "1") (pinfunction "+_1") (pintype "passive"))
      (node (ref "D12") (pin "17") (pinfunction "Gnd_17") (pintype "passive"))
      (node (ref "D12") (pin "4") (pinfunction "Gnd_4") (pintype "passive"))
      (node (ref "R132") (pin "2") (pinfunction "-_2") (pintype "passive"))
      (node (ref "R140") (pin "1") (pinfunction "+_1") (pintype "passive"))
      (node (ref "R142") (pin "1") (pinfunction "+_1") (pintype "passive"))
      (node (ref "R150") (pin "2") (pinfunction "-_2") (pintype "passive"))
    )
    (net (code "16") (name "GND_B") (class "Default")
      (node (ref "C102") (pin "1") (pinfunction "+_1") (pintype "passive"))
      (node (ref "D14") (pin "17") (pinfunction "Gnd_17") (pintype "passive"))
      (node (ref "D14") (pin "4") (pinfunction "Gnd_4") (pintype "passive"))
      (node (ref "R162") (pin "2") (pinfunction "-_2") (pintype "passive"))
      (node (ref "R166") (pin "1") (pinfunction "+_1") (pintype "passive"))
      (node (ref "R167") (pin "1") (pinfunction "+_1") (pintype "passive"))
      (node (ref "R168") (pin "2") (pinfunction "-_2") (pintype "passive"))
    )
    (net (code "17") (name "GND_C") (class "Default")
      (node (ref "D11") (pin "17") (pinfunction "PGND_17") (pintype "passive"))
      (node (ref "D11") (pin "4") (pinfunction "PGND_4") (pintype "passive"))
      (node (ref "D11") (pin "8") (pinfunction "PGND_8") (pintype "passive"))
      (node (ref "R138") (pin "2") (pinfunction "-_2") (pintype "passive"))
    )
    (net (code "18") (name "GND_D") (class "Default")
      (node (ref "D13") (pin "17") (pinfunction "PGND_17") (pintype "passive"))
      (node (ref "D13") (pin "4") (pinfunction "PGND_4") (pintype "passive"))
      (node (ref "D13") (pin "8") (pinfunction "PGND_8") (pintype "passive"))
      (node (ref "R163") (pin "2") (pinfunction "-_2") (pintype "passive"))
    )
    (net (code "19") (name "Net-(C65-+)") (class "Default")
      (node (ref "C65") (pin "1") (pinfunction "+_1") (pintype "passive"))
      (node (ref "C66") (pin "1") (pinfunction "+_1") (pintype "passive"))
      (node (ref "L7") (pin "2") (pinfunction "2_2") (pintype "passive"))
      (node (ref "R118") (pin "1") (pinfunction "+_1") (pintype "passive"))
      (node (ref "R119") (pin "2") (pinfunction "-_2") (pintype "passive"))
    )
    (net (code "20") (name "Net-(C72-+)") (class "Default")
      (node (ref "C72") (pin "1") (pinfunction "+_1") (pintype "passive"))
      (node (ref "C73") (pin "1") (pinfunction "+_1") (pintype "passive"))
      (node (ref "L8") (pin "2") (pinfunction "2_2") (pintype "passive"))
      (node (ref "R123") (pin "1") (pinfunction "+_1") (pintype "passive"))
      (node (ref "R126") (pin "2") (pinfunction "-_2") (pintype "passive"))
    )
    (net (code "21") (name "Net-(C74-+)") (class "Default")
      (node (ref "C74") (pin "1") (pinfunction "+_1") (pintype "passive"))
      (node (ref "R133") (pin "1") (pinfunction "+_1") (pintype "passive"))
    )
    (net (code "22") (name "Net-(C74--)") (class "Default")
      (node (ref "C74") (pin "2") (pinfunction "-_2") (pintype "passive"))
      (node (ref "C77") (pin "1") (pinfunction "+_1") (pintype "passive"))
      (node (ref "C78") (pin "1") (pinfunction "+_1") (pintype "passive"))
      (node (ref "L9") (pin "2") (pinfunction "2_2") (pintype "passive"))
      (node (ref "R121") (pin "1") (pinfunction "+_1") (pintype "passive"))
      (node (ref "R125") (pin "1") (pinfunction "+_1") (pintype "passive"))
      (node (ref "R128") (pin "2") (pinfunction "-_2") (pintype "passive"))
      (node (ref "R130") (pin "2") (pinfunction "-_2") (pintype "passive"))
    )
    (net (code "23") (name "Net-(C81--)") (class "Default")
      (node (ref "C81") (pin "2") (pinfunction "-_2") (pintype "passive"))
      (node (ref "D12") (pin "10") (pinfunction "Vcc_10") (pintype "passive"))
      (node (ref "D12") (pin "16") (pinfunction "Seq_16") (pintype "passive"))
    )
    (net (code "24") (name "Net-(C82--)") (class "Default")
      (node (ref "C82") (pin "2") (pinfunction "-_2") (pintype "passive"))
      (node (ref "D12") (pin "6") (pinfunction "SS/SD_6") (pintype "passive"))
    )
    (net (code "25") (name "Net-(C83-+)") (class "Default")
      (node (ref "C83") (pin "1") (pinfunction "+_1") (pintype "passive"))
      (node (ref "C84") (pin "2") (pinfunction "-_2") (pintype "passive"))
      (node (ref "D12") (pin "3") (pinfunction "Comp_3") (pintype "passive"))
    )
    (net (code "26") (name "Net-(C83--)") (class "Default")
      (node (ref "C83") (pin "2") (pinfunction "-_2") (pintype "passive"))
      (node (ref "R137") (pin "2") (pinfunction "-_2") (pintype "passive"))
    )
    (net (code "27") (name "Net-(C84-+)") (class "Default")
      (node (ref "C84") (pin "1") (pinfunction "+_1") (pintype "passive"))
      (node (ref "D12") (pin "1") (pinfunction "Fb_1") (pintype "passive"))
      (node (ref "R130") (pin "1") (pinfunction "+_1") (pintype "passive"))
      (node (ref "R133") (pin "2") (pinfunction "-_2") (pintype "passive"))
      (node (ref "R137") (pin "1") (pinfunction "+_1") (pintype "passive"))
      (node (ref "R140") (pin "2") (pinfunction "-_2") (pintype "passive"))
    )
    (net (code "28") (name "Net-(C85-+)") (class "Default")
      (node (ref "C85") (pin "1") (pinfunction "+_1") (pintype "passive"))
      (node (ref "C86") (pin "1") (pinfunction "+_1") (pintype "passive"))
      (node (ref "L10") (pin "2") (pinfunction "2_2") (pintype "passive"))
      (node (ref "R145") (pin "1") (pinfunction "+_1") (pintype "passive"))
      (node (ref "R147") (pin "2") (pinfunction "-_2") (pintype "passive"))
    )
    (net (code "29") (name "Net-(C91-+)") (class "Default")
      (node (ref "C91") (pin "1") (pinfunction "+_1") (pintype "passive"))
      (node (ref "C92") (pin "1") (pinfunction "+_1") (pintype "passive"))
      (node (ref "L11") (pin "2") (pinfunction "2_2") (pintype "passive"))
      (node (ref "R154") (pin "1") (pinfunction "+_1") (pintype "passive"))
      (node (ref "R155") (pin "2") (pinfunction "-_2") (pintype "passive"))
    )
    (net (code "30") (name "Net-(C93-+)") (class "Default")
      (node (ref "C93") (pin "1") (pinfunction "+_1") (pintype "passive"))
      (node (ref "D14") (pin "14") (pinfunction "Boot_14") (pintype "passive"))
    )
    (net (code "31") (name "Net-(C93--)") (class "Default")
      (node (ref "C93") (pin "2") (pinfunction "-_2") (pintype "passive"))
      (node (ref "D14") (pin "12") (pinfunction "SW_12") (pintype "passive"))
      (node (ref "L12") (pin "1") (pinfunction "1_1") (pintype "passive"))
      (node (ref "R159") (pin "1") (pinfunction "+_1") (pintype "passive"))
    )
    (net (code "32") (name "Net-(C101--)") (class "Default")
      (node (ref "C101") (pin "2") (pinfunction "-_2") (pintype "passive"))
      (node (ref "D14") (pin "10") (pinfunction "Vcc_10") (pintype "passive"))
      (node (ref "D14") (pin "16") (pinfunction "Seq_16") (pintype "passive"))
    )
    (net (code "33") (name "Net-(C102--)") (class "Default")
      (node (ref "C102") (pin "2") (pinfunction "-_2") (pintype "passive"))
      (node (ref "D14") (pin "6") (pinfunction "SS/SD_6") (pintype "passive"))
    )
    (net (code "34") (name "Net-(C104-+)") (class "Default")
      (node (ref "C104") (pin "1") (pinfunction "+_1") (pintype "passive"))
      (node (ref "D14") (pin "1") (pinfunction "Fb_1") (pintype "passive"))
      (node (ref "R161") (pin "1") (pinfunction "+_1") (pintype "passive"))
      (node (ref "R164") (pin "2") (pinfunction "-_2") (pintype "passive"))
      (node (ref "R165") (pin "1") (pinfunction "+_1") (pintype "passive"))
      (node (ref "R166") (pin "2") (pinfunction "-_2") (pintype "passive"))
    )
    (net (code "35") (name "Net-(C104--)") (class "Default")
      (node (ref "C104") (pin "2") (pinfunction "-_2") (pintype "passive"))
      (node (ref "C270") (pin "1") (pinfunction "+_1") (pintype "passive"))
      (node (ref "D14") (pin "3") (pinfunction "Comp_3") (pintype "passive"))
    )
    (net (code "36") (name "Net-(C267-+)") (class "Default")
      (node (ref "C267") (pin "1") (pinfunction "+_1") (pintype "passive"))
      (node (ref "D12") (pin "14") (pinfunction "Boot_14") (pintype "passive"))
    )
    (net (code "37") (name "Net-(C267--)") (class "Default")
      (node (ref "C267") (pin "2") (pinfunction "-_2") (pintype "passive"))
      (node (ref "D12") (pin "12") (pinfunction "SW_12") (pintype "passive"))
      (node (ref "L9") (pin "1") (pinfunction "1_1") (pintype "passive"))
      (node (ref "R129") (pin "1") (pinfunction "+_1") (pintype "passive"))
    )
    (net (code "38") (name "Net-(C269-+)") (class "Default")
      (node (ref "C269") (pin "1") (pinfunction "+_1") (pintype "passive"))
      (node (ref "R164") (pin "1") (pinfunction "+_1") (pintype "passive"))
    )
    (net (code "39") (name "Net-(C269--)") (class "Default")
      (node (ref "C269") (pin "2") (pinfunction "-_2") (pintype "passive"))
      (node (ref "C97") (pin "1") (pinfunction "+_1") (pintype "passive"))
      (node (ref "C98") (pin "1") (pinfunction "+_1") (pintype "passive"))
      (node (ref "L12") (pin "2") (pinfunction "2_2") (pintype "passive"))
      (node (ref "R156") (pin "1") (pinfunction "+_1") (pintype "passive"))
      (node (ref "R158") (pin "1") (pinfunction "+_1") (pintype "passive"))
      (node (ref "R160") (pin "2") (pinfunction "-_2") (pintype "passive"))
      (node (ref "R161") (pin "2") (pinfunction "-_2") (pintype "passive"))
    )
    (net (code "40") (name "Net-(C270--)") (class "Default")
      (node (ref "C270") (pin "2") (pinfunction "-_2") (pintype "passive"))
      (node (ref "R165") (pin "2") (pinfunction "-_2") (pintype "passive"))
    )
    (net (code "41") (name "Net-(D11-FB1)") (class "Default")
      (node (ref "D11") (pin "12") (pinfunction "FB1_12") (pintype "passive"))
      (node (ref "R119") (pin "1") (pinfunction "+_1") (pintype "passive"))
      (node (ref "R120") (pin "1") (pinfunction "+_1") (pintype "passive"))
    )
    (net (code "42") (name "Net-(D11-FB2)") (class "Default")
      (node (ref "D11") (pin "16") (pinfunction "FB2_16") (pintype "passive"))
      (node (ref "R126") (pin "1") (pinfunction "+_1") (pintype "passive"))
      (node (ref "R127") (pin "2") (pinfunction "-_2") (pintype "passive"))
    )
    (net (code "43") (name "Net-(D11-LX1)") (class "Default")
      (node (ref "D11") (pin "7") (pinfunction "LX1_7") (pintype "passive"))
      (node (ref "L7") (pin "1") (pinfunction "1_1") (pintype "passive"))
    )
    (net (code "44") (name "Net-(D11-LX2-Pad5)") (class "Default")
      (node (ref "D11") (pin "5") (pinfunction "LX2_5") (pintype "passive"))
      (node (ref "D11") (pin "6") (pinfunction "LX2_6") (pintype "passive"))
      (node (ref "L8") (pin "1") (pinfunction "1_1") (pintype "passive"))
    )
    (net (code "45") (name "Net-(D12-Enable)") (class "Default")
      (node (ref "D12") (pin "15") (pinfunction "Enable_15") (pintype "passive"))
      (node (ref "R122") (pin "2") (pinfunction "-_2") (pintype "passive"))
      (node (ref "R124") (pin "2") (pinfunction "-_2") (pintype "passive"))
    )
    (net (code "46") (name "Net-(D12-OCSet)") (class "Default")
      (node (ref "D12") (pin "7") (pinfunction "OCSet_7") (pintype "passive"))
      (node (ref "R129") (pin "2") (pinfunction "-_2") (pintype "passive"))
    )
    (net (code "47") (name "Net-(D12-Rt)") (class "Default")
      (node (ref "D12") (pin "5") (pinfunction "Rt_5") (pintype "passive"))
      (node (ref "R132") (pin "1") (pinfunction "+_1") (pintype "passive"))
    )
    (net (code "48") (name "Net-(D12-Vsns)") (class "Default")
      (node (ref "D12") (pin "2") (pinfunction "Vsns_2") (pintype "passive"))
      (node (ref "R128") (pin "1") (pinfunction "+_1") (pintype "passive"))
      (node (ref "R142") (pin "2") (pinfunction "-_2") (pintype "passive"))
    )
    (net (code "49") (name "Net-(D13-FB1)") (class "Default")
      (node (ref "D13") (pin "12") (pinfunction "FB1_12") (pintype "passive"))
      (node (ref "R147") (pin "1") (pinfunction "+_1") (pintype "passive"))
      (node (ref "R151") (pin "1") (pinfunction "+_1") (pintype "passive"))
    )
    (net (code "50") (name "Net-(D13-FB2)") (class "Default")
      (node (ref "D13") (pin "16") (pinfunction "FB2_16") (pintype "passive"))
      (node (ref "R155") (pin "1") (pinfunction "+_1") (pintype "passive"))
      (node (ref "R157") (pin "2") (pinfunction "-_2") (pintype "passive"))
    )
    (net (code "51") (name "Net-(D13-LX1)") (class "Default")
      (node (ref "D13") (pin "7") (pinfunction "LX1_7") (pintype "passive"))
      (node (ref "L10") (pin "1") (pinfunction "1_1") (pintype "passive"))
    )
    (net (code "52") (name "Net-(D13-LX2-Pad5)") (class "Default")
      (node (ref "D13") (pin "5") (pinfunction "LX2_5") (pintype "passive"))
      (node (ref "D13") (pin "6") (pinfunction "LX2_6") (pintype "passive"))
      (node (ref "L11") (pin "1") (pinfunction "1_1") (pintype "passive"))
    )
    (net (code "53") (name "Net-(D14-OCSet)") (class "Default")
      (node (ref "D14") (pin "7") (pinfunction "OCSet_7") (pintype "passive"))
      (node (ref "R159") (pin "2") (pinfunction "-_2") (pintype "passive"))
    )
    (net (code "54") (name "Net-(D14-Rt)") (class "Default")
      (node (ref "D14") (pin "5") (pinfunction "Rt_5") (pintype "passive"))
      (node (ref "R162") (pin "1") (pinfunction "+_1") (pintype "passive"))
    )
    (net (code "55") (name "Net-(D14-Vsns)") (class "Default")
      (node (ref "D14") (pin "2") (pinfunction "Vsns_2") (pintype "passive"))
      (node (ref "R160") (pin "1") (pinfunction "+_1") (pintype "passive"))
      (node (ref "R167") (pin "2") (pinfunction "-_2") (pintype "passive"))
    )
    (net (code "56") (name "Net-(R131-+)") (class "Default")
      (node (ref "R131") (pin "1") (pinfunction "+_1") (pintype "passive"))
      (node (ref "R134") (pin "2") (pinfunction "-_2") (pintype "passive"))
      (node (ref "R135") (pin "1") (pinfunction "+_1") (pintype "passive"))
      (node (ref "R136") (pin "1") (pinfunction "+_1") (pintype "passive"))
      (node (ref "R139") (pin "2") (pinfunction "-_2") (pintype "passive"))
      (node (ref "R141") (pin "1") (pinfunction "+_1") (pintype "passive"))
      (node (ref "R143") (pin "1") (pinfunction "+_1") (pintype "passive"))
    )
    (net (code "57") (name "VCC1P1") (class "Default")
      (node (ref "C100") (pin "1") (pinfunction "+_1") (pintype "passive"))
      (node (ref "C99") (pin "1") (pinfunction "+_1") (pintype "passive"))
      (node (ref "R156") (pin "2") (pinfunction "-_2") (pintype "passive"))
      (node (ref "R158") (pin "2") (pinfunction "-_2") (pintype "passive"))
    )
    (net (code "58") (name "VCC1P2") (class "Default")
      (node (ref "R145") (pin "2") (pinfunction "-_2") (pintype "passive"))
    )
    (net (code "59") (name "VCC1P8") (class "Default")
      (node (ref "R118") (pin "2") (pinfunction "-_2") (pintype "passive"))
    )
    (net (code "60") (name "VCC1P35_DDR3") (class "Default")
      (node (ref "R154") (pin "2") (pinfunction "-_2") (pintype "passive"))
    )
    (net (code "61") (name "VCC2P5") (class "Default")
      (node (ref "R123") (pin "2") (pinfunction "-_2") (pintype "passive"))
    )
    (net (code "62") (name "VCC3P3") (class "Default")
      (node (ref "C268") (pin "1") (pinfunction "+_1") (pintype "passive"))
      (node (ref "C67") (pin "1") (pinfunction "+_1") (pintype "passive"))
      (node (ref "C71") (pin "1") (pinfunction "+_1") (pintype "passive"))
      (node (ref "C79") (pin "1") (pinfunction "+_1") (pintype "passive"))
      (node (ref "C80") (pin "1") (pinfunction "+_1") (pintype "passive"))
      (node (ref "C88") (pin "1") (pinfunction "+_1") (pintype "passive"))
      (node (ref "D11") (pin "10") (pinfunction "VDD_10") (pintype "passive"))
      (node (ref "D11") (pin "2") (pinfunction "PVDD2_2") (pintype "passive"))
      (node (ref "D11") (pin "3") (pinfunction "PVDD2_3") (pintype "passive"))
      (node (ref "D11") (pin "9") (pinfunction "PVDD1_9") (pintype "passive"))
      (node (ref "D13") (pin "10") (pinfunction "VDD_10") (pintype "passive"))
      (node (ref "D13") (pin "2") (pinfunction "PVDD2_2") (pintype "passive"))
      (node (ref "D13") (pin "3") (pinfunction "PVDD2_3") (pintype "passive"))
      (node (ref "D13") (pin "9") (pinfunction "PVDD1_9") (pintype "passive"))
      (node (ref "R121") (pin "2") (pinfunction "-_2") (pintype "passive"))
      (node (ref "R125") (pin "2") (pinfunction "-_2") (pintype "passive"))
      (node (ref "R131") (pin "2") (pinfunction "-_2") (pintype "passive"))
      (node (ref "R148") (pin "2") (pinfunction "-_2") (pintype "passive"))
      (node (ref "R217") (pin "2") (pinfunction "-_2") (pintype "passive"))
    )
    (net (code "63") (name "VIN") (class "Default")
      (node (ref "C68") (pin "1") (pinfunction "+_1") (pintype "passive"))
      (node (ref "C69") (pin "1") (pinfunction "+_1") (pintype "passive"))
      (node (ref "C75") (pin "1") (pinfunction "+_1") (pintype "passive"))
      (node (ref "C76") (pin "1") (pinfunction "+_1") (pintype "passive"))
      (node (ref "C89") (pin "1") (pinfunction "+_1") (pintype "passive"))
      (node (ref "C90") (pin "1") (pinfunction "+_1") (pintype "passive"))
      (node (ref "C95") (pin "1") (pinfunction "+_1") (pintype "passive"))
      (node (ref "C96") (pin "1") (pinfunction "+_1") (pintype "passive"))
      (node (ref "D12") (pin "13") (pinfunction "Vin_13") (pintype "passive"))
      (node (ref "D14") (pin "13") (pinfunction "Vin_13") (pintype "passive"))
      (node (ref "R122") (pin "1") (pinfunction "+_1") (pintype "passive"))
    )
    (net (code "64") (name "unconnected-(D12-Sync-Pad9)") (class "Default")
      (node (ref "D12") (pin "9") (pinfunction "Sync_9") (pintype "passive"))
    )
    (net (code "65") (name "unconnected-(D14-Sync-Pad9)") (class "Default")
      (node (ref "D14") (pin "9") (pinfunction "Sync_9") (pintype "passive"))
    )
  )
)
